# gps_auxiliary.net
KiCad netlist of a schematic drawn in EAGLE
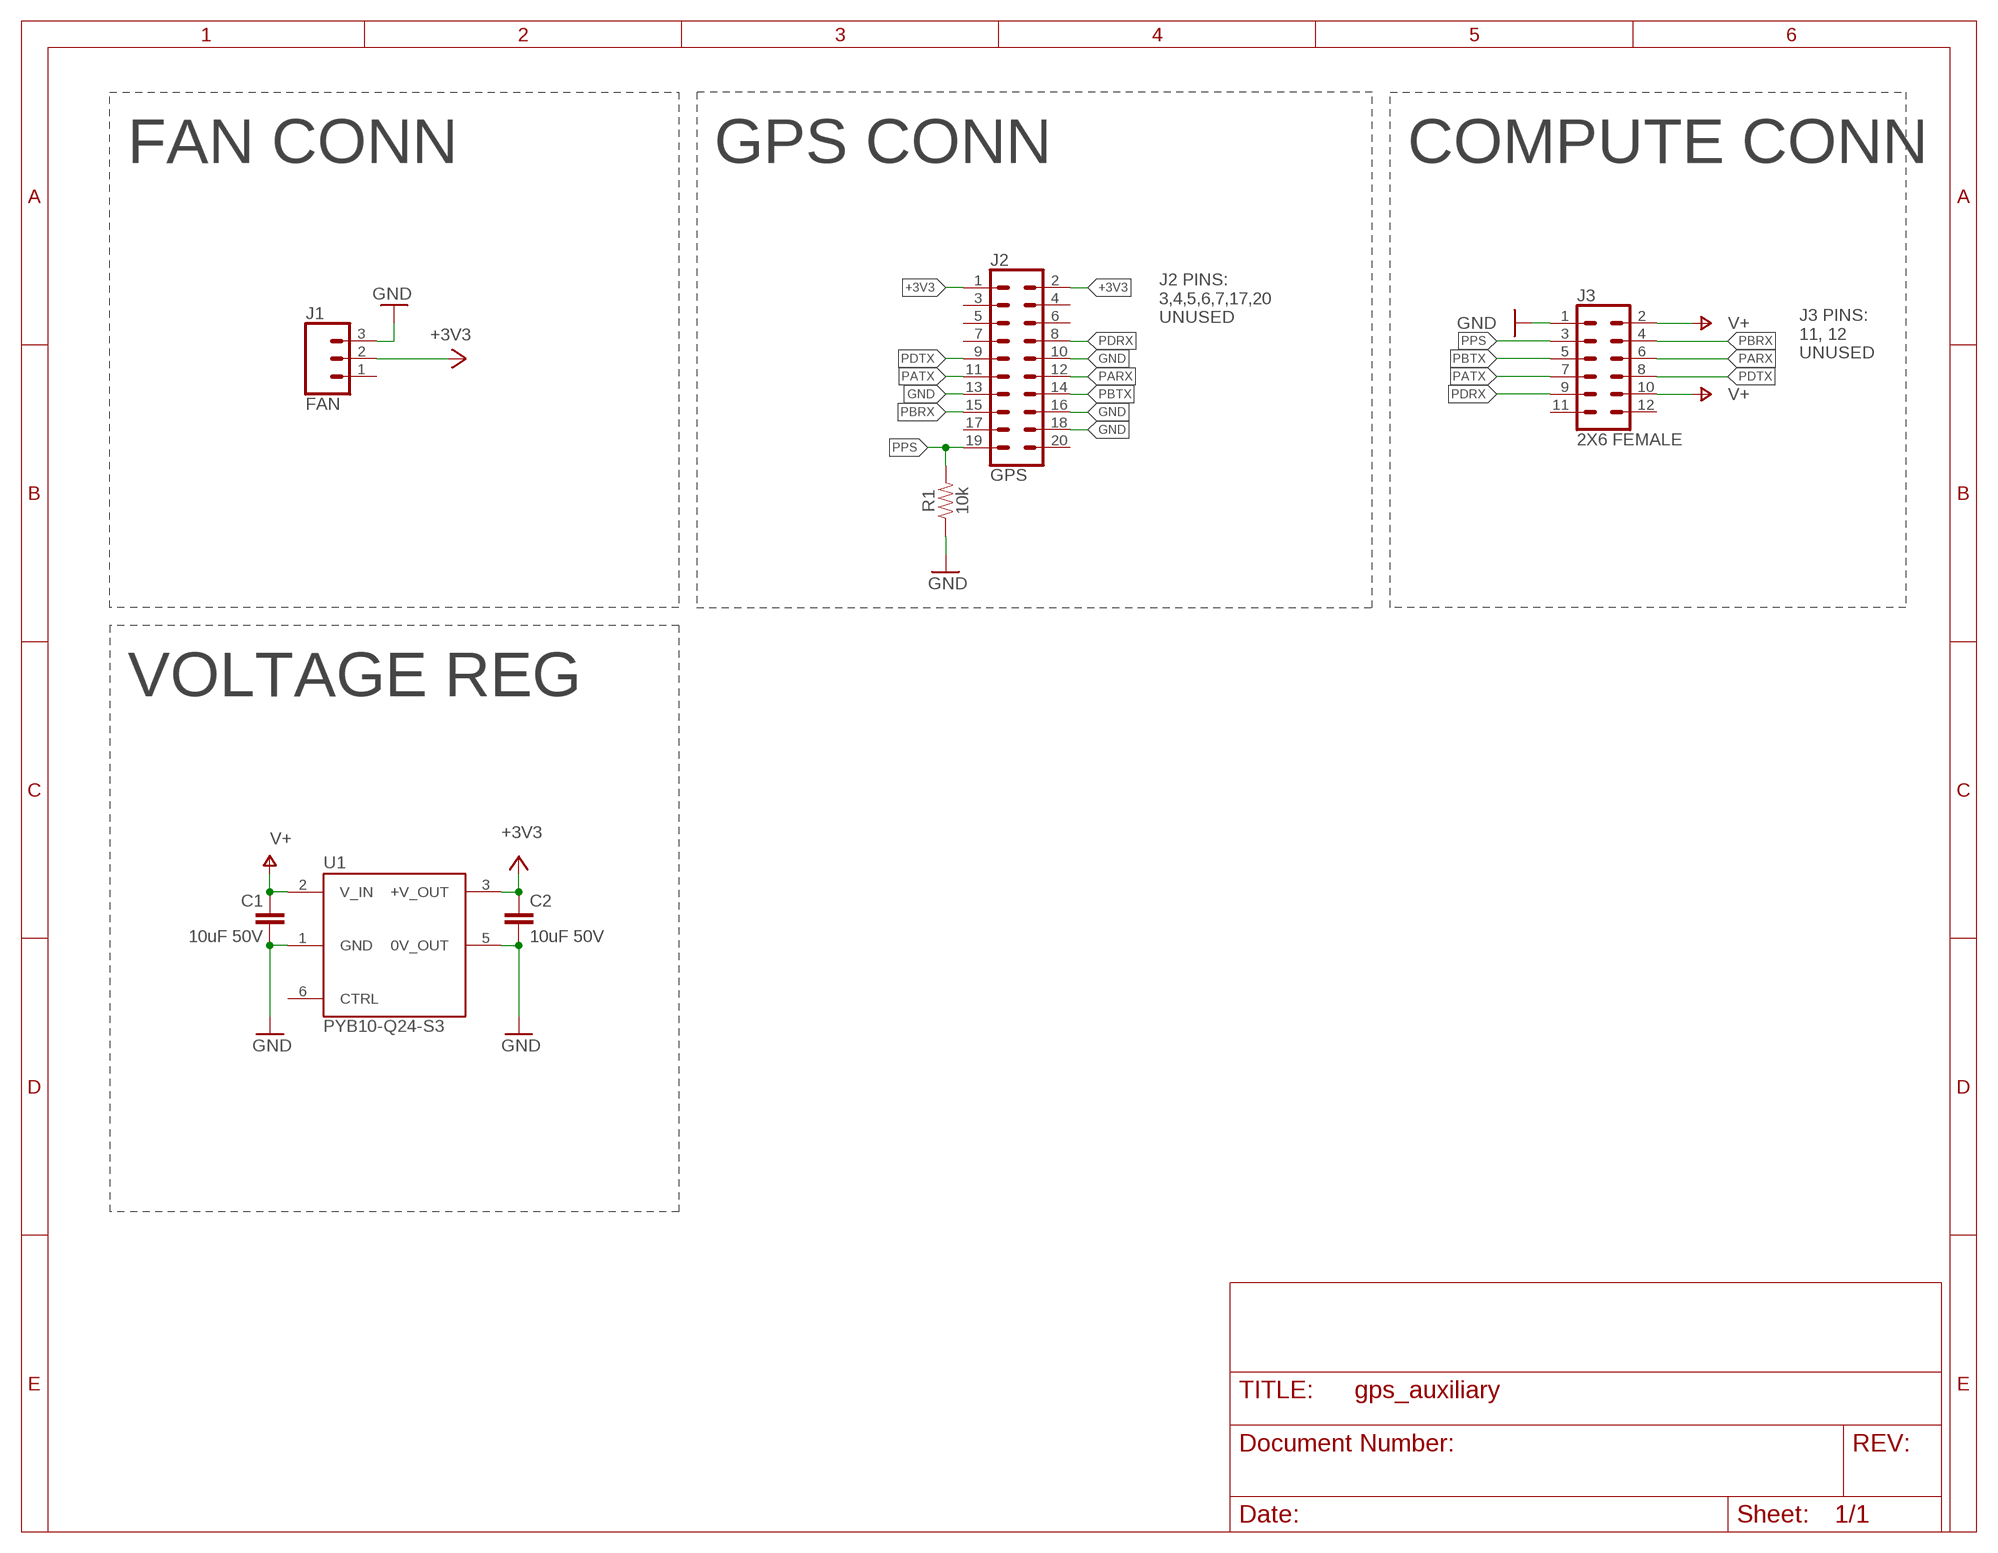
[diagram p0: schematic, sheet 1]

(export (version "E")
  (design (tool "Eeschema 10.0.6"))
  (components
    (comp (ref "C1")
      (value "10uF 50V")
      (footprint "eagle-import:CAP-PTH-5MM")
      (libsource (lib "eagle-import") (part "CAP-5MM"))
    )
    (comp (ref "C2")
      (value "10uF 50V")
      (footprint "eagle-import:CAP-PTH-5MM")
      (libsource (lib "eagle-import") (part "CAP-5MM"))
    )
    (comp (ref "J1")
      (value "FAN")
      (footprint "eagle-import:ED700")
      (libsource (lib "eagle-import") (part "ED700/3"))
    )
    (comp (ref "J2")
      (value "GPS")
      (footprint "eagle-import:EHT-110-01-S-D")
      (libsource (lib "eagle-import") (part "EHT-110-01-S-D"))
    )
    (comp (ref "J3")
      (value "2X6 FEMALE")
      (footprint "eagle-import:2X6")
      (libsource (lib "eagle-import") (part "CONN_06X2PTH_FEMALE"))
    )
    (comp (ref "R1")
      (value "10k")
      (footprint "eagle-import:AXIAL-0.3")
      (libsource (lib "eagle-import") (part "CFR-25JB-52-10K"))
    )
    (comp (ref "U1")
      (value "PYB10-Q24-S3")
      (footprint "eagle-import:PYB10")
      (libsource (lib "eagle-import") (part "PYB10-Q24-S3"))
    )
  )
  (nets
    (net (code "1") (name "+3V3") (class "Default")
      (node (ref "C2") (pin "1") (pinfunction "1_1") (pintype "passive"))
      (node (ref "J1") (pin "2") (pinfunction "2_2") (pintype "passive"))
      (node (ref "J2") (pin "1") (pinfunction "1_1") (pintype "passive"))
      (node (ref "J2") (pin "2") (pinfunction "2_2") (pintype "passive"))
      (node (ref "U1") (pin "3") (pinfunction "+V_OUT_3") (pintype "output"))
    )
    (net (code "2") (name "GND") (class "Default")
      (node (ref "C1") (pin "2") (pinfunction "2_2") (pintype "passive"))
      (node (ref "C2") (pin "2") (pinfunction "2_2") (pintype "passive"))
      (node (ref "J1") (pin "3") (pinfunction "3_3") (pintype "passive"))
      (node (ref "J2") (pin "10") (pinfunction "10_10") (pintype "passive"))
      (node (ref "J2") (pin "13") (pinfunction "13_13") (pintype "passive"))
      (node (ref "J2") (pin "16") (pinfunction "16_16") (pintype "passive"))
      (node (ref "J2") (pin "18") (pinfunction "18_18") (pintype "passive"))
      (node (ref "J3") (pin "1") (pinfunction "1_1") (pintype "passive"))
      (node (ref "R1") (pin "1") (pinfunction "1_1") (pintype "passive"))
      (node (ref "U1") (pin "1") (pinfunction "GND_1") (pintype "power_in"))
      (node (ref "U1") (pin "5") (pinfunction "0V_OUT_5") (pintype "output"))
    )
    (net (code "3") (name "PARX") (class "Default")
      (node (ref "J2") (pin "12") (pinfunction "12_12") (pintype "passive"))
      (node (ref "J3") (pin "6") (pinfunction "6_6") (pintype "passive"))
    )
    (net (code "4") (name "PATX") (class "Default")
      (node (ref "J2") (pin "11") (pinfunction "11_11") (pintype "passive"))
      (node (ref "J3") (pin "7") (pinfunction "7_7") (pintype "passive"))
    )
    (net (code "5") (name "PBRX") (class "Default")
      (node (ref "J2") (pin "15") (pinfunction "15_15") (pintype "passive"))
      (node (ref "J3") (pin "4") (pinfunction "4_4") (pintype "passive"))
    )
    (net (code "6") (name "PBTX") (class "Default")
      (node (ref "J2") (pin "14") (pinfunction "14_14") (pintype "passive"))
      (node (ref "J3") (pin "5") (pinfunction "5_5") (pintype "passive"))
    )
    (net (code "7") (name "PDRX") (class "Default")
      (node (ref "J2") (pin "8") (pinfunction "8_8") (pintype "passive"))
      (node (ref "J3") (pin "9") (pinfunction "9_9") (pintype "passive"))
    )
    (net (code "8") (name "PDTX") (class "Default")
      (node (ref "J2") (pin "9") (pinfunction "9_9") (pintype "passive"))
      (node (ref "J3") (pin "8") (pinfunction "8_8") (pintype "passive"))
    )
    (net (code "9") (name "PPS") (class "Default")
      (node (ref "J2") (pin "19") (pinfunction "19_19") (pintype "passive"))
      (node (ref "J3") (pin "3") (pinfunction "3_3") (pintype "passive"))
      (node (ref "R1") (pin "2") (pinfunction "2_2") (pintype "passive"))
    )
    (net (code "10") (name "V+") (class "Default")
      (node (ref "C1") (pin "1") (pinfunction "1_1") (pintype "passive"))
      (node (ref "J3") (pin "10") (pinfunction "10_10") (pintype "passive"))
      (node (ref "J3") (pin "2") (pinfunction "2_2") (pintype "passive"))
      (node (ref "U1") (pin "2") (pinfunction "V_IN_2") (pintype "power_in"))
    )
    (net (code "11") (name "unconnected-(J1-Pad1)") (class "Default")
      (node (ref "J1") (pin "1") (pinfunction "1_1") (pintype "passive"))
    )
    (net (code "12") (name "unconnected-(J2-Pad3)") (class "Default")
      (node (ref "J2") (pin "3") (pinfunction "3_3") (pintype "passive"))
    )
    (net (code "13") (name "unconnected-(J2-Pad4)") (class "Default")
      (node (ref "J2") (pin "4") (pinfunction "4_4") (pintype "passive"))
    )
    (net (code "14") (name "unconnected-(J2-Pad5)") (class "Default")
      (node (ref "J2") (pin "5") (pinfunction "5_5") (pintype "passive"))
    )
    (net (code "15") (name "unconnected-(J2-Pad6)") (class "Default")
      (node (ref "J2") (pin "6") (pinfunction "6_6") (pintype "passive"))
    )
    (net (code "16") (name "unconnected-(J2-Pad7)") (class "Default")
      (node (ref "J2") (pin "7") (pinfunction "7_7") (pintype "passive"))
    )
    (net (code "17") (name "unconnected-(J2-Pad17)") (class "Default")
      (node (ref "J2") (pin "17") (pinfunction "17_17") (pintype "passive"))
    )
    (net (code "18") (name "unconnected-(J2-Pad20)") (class "Default")
      (node (ref "J2") (pin "20") (pinfunction "20_20") (pintype "passive"))
    )
    (net (code "19") (name "unconnected-(J3-Pad11)") (class "Default")
      (node (ref "J3") (pin "11") (pinfunction "11_11") (pintype "passive"))
    )
    (net (code "20") (name "unconnected-(J3-Pad12)") (class "Default")
      (node (ref "J3") (pin "12") (pinfunction "12_12") (pintype "passive"))
    )
    (net (code "21") (name "unconnected-(U1-CTRL-Pad6)") (class "Default")
      (node (ref "U1") (pin "6") (pinfunction "CTRL_6") (pintype "bidirectional"))
    )
  )
)
